# MEGA2560v3ProtoShield.net
KiCad netlist of a schematic drawn in EAGLE
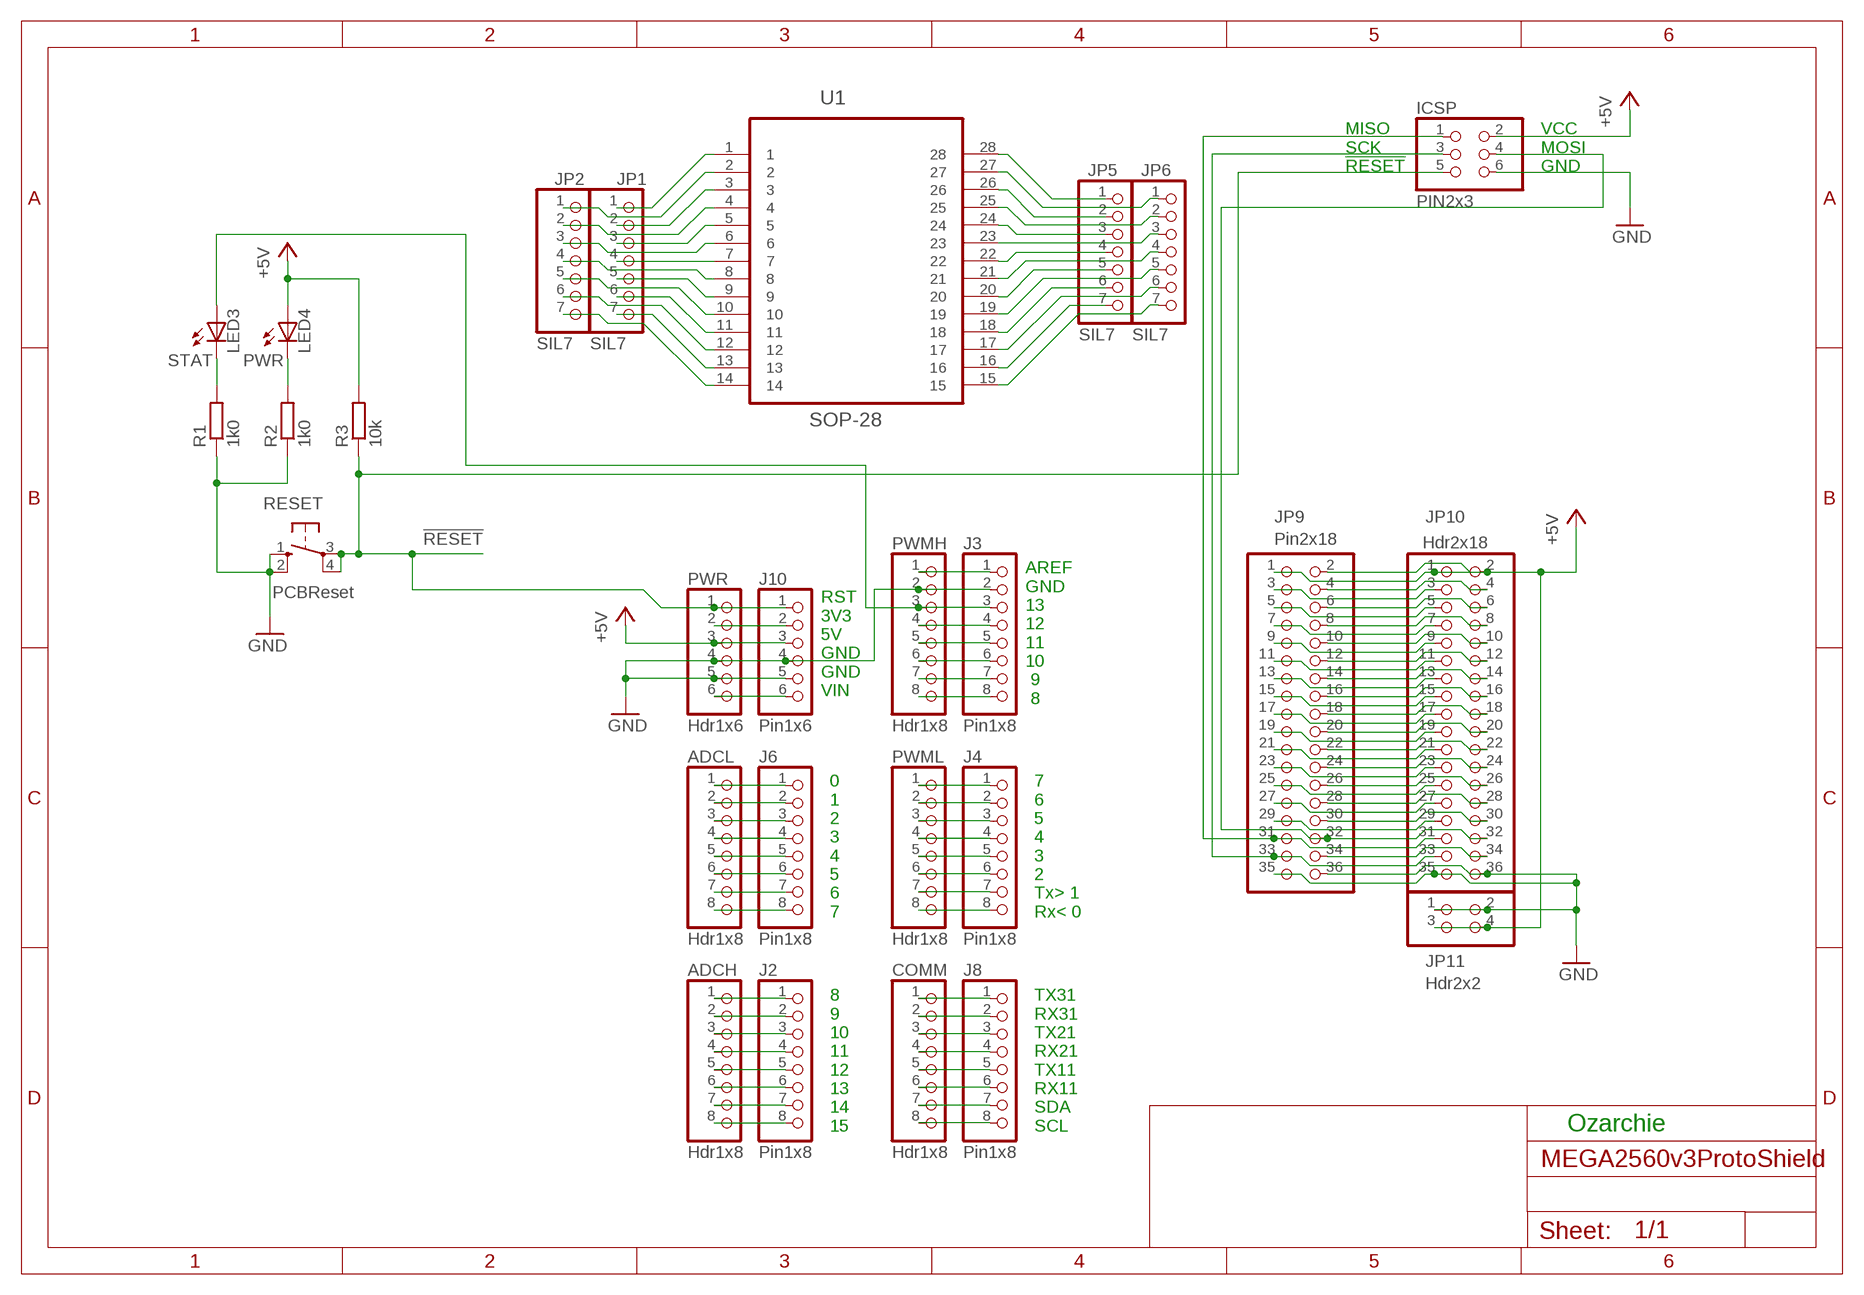
[diagram p0: schematic, sheet 1]

(export (version "E")
  (design (tool "Eeschema 10.0.6"))
  (components
    (comp (ref "ADCH")
      (value "Hdr1x8")
      (footprint "eagle-import:1X08")
      (libsource (lib "eagle-import") (part "PINHD-1X8"))
    )
    (comp (ref "ADCL")
      (value "Hdr1x8")
      (footprint "eagle-import:1X08")
      (libsource (lib "eagle-import") (part "PINHD-1X8"))
    )
    (comp (ref "COMM")
      (value "Hdr1x8")
      (footprint "eagle-import:1X08")
      (libsource (lib "eagle-import") (part "PINHD-1X8"))
    )
    (comp (ref "ICSP")
      (value "PIN2x3")
      (footprint "eagle-import:2X03")
      (libsource (lib "eagle-import") (part "PINHD-2X3"))
    )
    (comp (ref "J2")
      (value "Pin1x8")
      (footprint "eagle-import:1X08")
      (libsource (lib "eagle-import") (part "PINHD-1X8"))
    )
    (comp (ref "J3")
      (value "Pin1x8")
      (footprint "eagle-import:1X08")
      (libsource (lib "eagle-import") (part "PINHD-1X8"))
    )
    (comp (ref "J4")
      (value "Pin1x8")
      (footprint "eagle-import:1X08")
      (libsource (lib "eagle-import") (part "PINHD-1X8"))
    )
    (comp (ref "J6")
      (value "Pin1x8")
      (footprint "eagle-import:1X08")
      (libsource (lib "eagle-import") (part "PINHD-1X8"))
    )
    (comp (ref "J8")
      (value "Pin1x8")
      (footprint "eagle-import:1X08")
      (libsource (lib "eagle-import") (part "PINHD-1X8"))
    )
    (comp (ref "J10")
      (value "Pin1x6")
      (footprint "eagle-import:1X06")
      (libsource (lib "eagle-import") (part "PINHD-1X6"))
    )
    (comp (ref "JP1")
      (value "SIL7")
      (footprint "eagle-import:1X07")
      (libsource (lib "eagle-import") (part "PINHD-1X7"))
    )
    (comp (ref "JP2")
      (value "SIL7")
      (footprint "eagle-import:1X07")
      (libsource (lib "eagle-import") (part "PINHD-1X7"))
    )
    (comp (ref "JP5")
      (value "SIL7")
      (footprint "eagle-import:1X07")
      (libsource (lib "eagle-import") (part "PINHD-1X7"))
    )
    (comp (ref "JP6")
      (value "SIL7")
      (footprint "eagle-import:1X07")
      (libsource (lib "eagle-import") (part "PINHD-1X7"))
    )
    (comp (ref "JP9")
      (value "Pin2x18")
      (footprint "eagle-import:2X18")
      (libsource (lib "eagle-import") (part "PINHD-2X18"))
    )
    (comp (ref "JP10")
      (value "Hdr2x18")
      (footprint "eagle-import:2X18")
      (libsource (lib "eagle-import") (part "PINHD-2X18"))
    )
    (comp (ref "JP11")
      (value "Hdr2x2")
      (footprint "eagle-import:2X02")
      (libsource (lib "eagle-import") (part "PINHD-2X2"))
    )
    (comp (ref "LED3")
      (value "STAT")
      (footprint "eagle-import:CHIPLED_1206")
      (libsource (lib "eagle-import") (part "LEDCHIPLED_1206"))
    )
    (comp (ref "LED4")
      (value "PWR")
      (footprint "eagle-import:CHIPLED_1206")
      (libsource (lib "eagle-import") (part "LEDCHIPLED_1206"))
    )
    (comp (ref "PWMH")
      (value "Hdr1x8")
      (footprint "eagle-import:1X08")
      (libsource (lib "eagle-import") (part "PINHD-1X8"))
    )
    (comp (ref "PWML")
      (value "Hdr1x8")
      (footprint "eagle-import:1X08")
      (libsource (lib "eagle-import") (part "PINHD-1X8"))
    )
    (comp (ref "PWR")
      (value "Hdr1x6")
      (footprint "eagle-import:1X06")
      (libsource (lib "eagle-import") (part "PINHD-1X6"))
    )
    (comp (ref "R1")
      (value "1k0")
      (footprint "eagle-import:R0805")
      (libsource (lib "eagle-import") (part "R-EU_R0805"))
    )
    (comp (ref "R2")
      (value "1k0")
      (footprint "eagle-import:R0805")
      (libsource (lib "eagle-import") (part "R-EU_R0805"))
    )
    (comp (ref "R3")
      (value "10k")
      (footprint "eagle-import:R0805")
      (libsource (lib "eagle-import") (part "R-EU_R0805"))
    )
    (comp (ref "RESET")
      (value "PCBReset")
      (footprint "eagle-import:B3F-10XX")
      (fields (field (name "MPN") "B3F-1000"))
      (libsource (lib "eagle-import") (part "10-XX"))
    )
    (comp (ref "U1")
      (value "SOP-28")
      (footprint "eagle-import:SOP50P1030X264-28N")
      (libsource (lib "eagle-import") (part "SOP-28"))
    )
  )
  (nets
    (net (code "1") (name "+5V") (class "Default")
      (node (ref "ICSP") (pin "2") (pinfunction "2_2") (pintype "passive"))
      (node (ref "J10") (pin "3") (pinfunction "3_3") (pintype "passive"))
      (node (ref "JP10") (pin "1") (pinfunction "1_1") (pintype "passive"))
      (node (ref "JP10") (pin "2") (pinfunction "2_2") (pintype "passive"))
      (node (ref "JP11") (pin "3") (pinfunction "3_3") (pintype "passive"))
      (node (ref "JP11") (pin "4") (pinfunction "4_4") (pintype "passive"))
      (node (ref "JP9") (pin "1") (pinfunction "1_1") (pintype "passive"))
      (node (ref "JP9") (pin "2") (pinfunction "2_2") (pintype "passive"))
      (node (ref "LED4") (pin "A") (pinfunction "A_A") (pintype "passive"))
      (node (ref "PWR") (pin "3") (pinfunction "3_3") (pintype "passive"))
      (node (ref "R3") (pin "2") (pinfunction "2_2") (pintype "passive"))
    )
    (net (code "2") (name "/~{RESET}") (class "Default")
      (node (ref "ICSP") (pin "5") (pinfunction "5_5") (pintype "passive"))
      (node (ref "J10") (pin "1") (pinfunction "1_1") (pintype "passive"))
      (node (ref "PWR") (pin "1") (pinfunction "1_1") (pintype "passive"))
      (node (ref "R3") (pin "1") (pinfunction "1_1") (pintype "passive"))
      (node (ref "RESET") (pin "3") (pinfunction "P_3") (pintype "passive"))
      (node (ref "RESET") (pin "4") (pinfunction "P1_4") (pintype "passive"))
    )
    (net (code "3") (name "GND") (class "Default")
      (node (ref "ICSP") (pin "6") (pinfunction "6_6") (pintype "passive"))
      (node (ref "J10") (pin "4") (pinfunction "4_4") (pintype "passive"))
      (node (ref "J10") (pin "5") (pinfunction "5_5") (pintype "passive"))
      (node (ref "J3") (pin "2") (pinfunction "2_2") (pintype "passive"))
      (node (ref "JP10") (pin "35") (pinfunction "35_35") (pintype "passive"))
      (node (ref "JP10") (pin "36") (pinfunction "36_36") (pintype "passive"))
      (node (ref "JP11") (pin "1") (pinfunction "1_1") (pintype "passive"))
      (node (ref "JP11") (pin "2") (pinfunction "2_2") (pintype "passive"))
      (node (ref "JP9") (pin "35") (pinfunction "35_35") (pintype "passive"))
      (node (ref "JP9") (pin "36") (pinfunction "36_36") (pintype "passive"))
      (node (ref "PWMH") (pin "2") (pinfunction "2_2") (pintype "passive"))
      (node (ref "PWR") (pin "4") (pinfunction "4_4") (pintype "passive"))
      (node (ref "PWR") (pin "5") (pinfunction "5_5") (pintype "passive"))
      (node (ref "R1") (pin "1") (pinfunction "1_1") (pintype "passive"))
      (node (ref "R2") (pin "1") (pinfunction "1_1") (pintype "passive"))
      (node (ref "RESET") (pin "1") (pinfunction "S_1") (pintype "passive"))
      (node (ref "RESET") (pin "2") (pinfunction "S1_2") (pintype "passive"))
    )
    (net (code "4") (name "Net-(ADCH-Pad1)") (class "Default")
      (node (ref "ADCH") (pin "1") (pinfunction "1_1") (pintype "passive"))
      (node (ref "J2") (pin "1") (pinfunction "1_1") (pintype "passive"))
    )
    (net (code "5") (name "Net-(ADCH-Pad2)") (class "Default")
      (node (ref "ADCH") (pin "2") (pinfunction "2_2") (pintype "passive"))
      (node (ref "J2") (pin "2") (pinfunction "2_2") (pintype "passive"))
    )
    (net (code "6") (name "Net-(ADCH-Pad3)") (class "Default")
      (node (ref "ADCH") (pin "3") (pinfunction "3_3") (pintype "passive"))
      (node (ref "J2") (pin "3") (pinfunction "3_3") (pintype "passive"))
    )
    (net (code "7") (name "Net-(ADCH-Pad4)") (class "Default")
      (node (ref "ADCH") (pin "4") (pinfunction "4_4") (pintype "passive"))
      (node (ref "J2") (pin "4") (pinfunction "4_4") (pintype "passive"))
    )
    (net (code "8") (name "Net-(ADCH-Pad5)") (class "Default")
      (node (ref "ADCH") (pin "5") (pinfunction "5_5") (pintype "passive"))
      (node (ref "J2") (pin "5") (pinfunction "5_5") (pintype "passive"))
    )
    (net (code "9") (name "Net-(ADCH-Pad6)") (class "Default")
      (node (ref "ADCH") (pin "6") (pinfunction "6_6") (pintype "passive"))
      (node (ref "J2") (pin "6") (pinfunction "6_6") (pintype "passive"))
    )
    (net (code "10") (name "Net-(ADCH-Pad7)") (class "Default")
      (node (ref "ADCH") (pin "7") (pinfunction "7_7") (pintype "passive"))
      (node (ref "J2") (pin "7") (pinfunction "7_7") (pintype "passive"))
    )
    (net (code "11") (name "Net-(ADCH-Pad8)") (class "Default")
      (node (ref "ADCH") (pin "8") (pinfunction "8_8") (pintype "passive"))
      (node (ref "J2") (pin "8") (pinfunction "8_8") (pintype "passive"))
    )
    (net (code "12") (name "Net-(ADCL-Pad1)") (class "Default")
      (node (ref "ADCL") (pin "1") (pinfunction "1_1") (pintype "passive"))
      (node (ref "J6") (pin "1") (pinfunction "1_1") (pintype "passive"))
    )
    (net (code "13") (name "Net-(ADCL-Pad2)") (class "Default")
      (node (ref "ADCL") (pin "2") (pinfunction "2_2") (pintype "passive"))
      (node (ref "J6") (pin "2") (pinfunction "2_2") (pintype "passive"))
    )
    (net (code "14") (name "Net-(ADCL-Pad3)") (class "Default")
      (node (ref "ADCL") (pin "3") (pinfunction "3_3") (pintype "passive"))
      (node (ref "J6") (pin "3") (pinfunction "3_3") (pintype "passive"))
    )
    (net (code "15") (name "Net-(ADCL-Pad4)") (class "Default")
      (node (ref "ADCL") (pin "4") (pinfunction "4_4") (pintype "passive"))
      (node (ref "J6") (pin "4") (pinfunction "4_4") (pintype "passive"))
    )
    (net (code "16") (name "Net-(ADCL-Pad5)") (class "Default")
      (node (ref "ADCL") (pin "5") (pinfunction "5_5") (pintype "passive"))
      (node (ref "J6") (pin "5") (pinfunction "5_5") (pintype "passive"))
    )
    (net (code "17") (name "Net-(ADCL-Pad6)") (class "Default")
      (node (ref "ADCL") (pin "6") (pinfunction "6_6") (pintype "passive"))
      (node (ref "J6") (pin "6") (pinfunction "6_6") (pintype "passive"))
    )
    (net (code "18") (name "Net-(ADCL-Pad7)") (class "Default")
      (node (ref "ADCL") (pin "7") (pinfunction "7_7") (pintype "passive"))
      (node (ref "J6") (pin "7") (pinfunction "7_7") (pintype "passive"))
    )
    (net (code "19") (name "Net-(ADCL-Pad8)") (class "Default")
      (node (ref "ADCL") (pin "8") (pinfunction "8_8") (pintype "passive"))
      (node (ref "J6") (pin "8") (pinfunction "8_8") (pintype "passive"))
    )
    (net (code "20") (name "Net-(COMM-Pad1)") (class "Default")
      (node (ref "COMM") (pin "1") (pinfunction "1_1") (pintype "passive"))
      (node (ref "J8") (pin "1") (pinfunction "1_1") (pintype "passive"))
    )
    (net (code "21") (name "Net-(COMM-Pad2)") (class "Default")
      (node (ref "COMM") (pin "2") (pinfunction "2_2") (pintype "passive"))
      (node (ref "J8") (pin "2") (pinfunction "2_2") (pintype "passive"))
    )
    (net (code "22") (name "Net-(COMM-Pad3)") (class "Default")
      (node (ref "COMM") (pin "3") (pinfunction "3_3") (pintype "passive"))
      (node (ref "J8") (pin "3") (pinfunction "3_3") (pintype "passive"))
    )
    (net (code "23") (name "Net-(COMM-Pad4)") (class "Default")
      (node (ref "COMM") (pin "4") (pinfunction "4_4") (pintype "passive"))
      (node (ref "J8") (pin "4") (pinfunction "4_4") (pintype "passive"))
    )
    (net (code "24") (name "Net-(COMM-Pad5)") (class "Default")
      (node (ref "COMM") (pin "5") (pinfunction "5_5") (pintype "passive"))
      (node (ref "J8") (pin "5") (pinfunction "5_5") (pintype "passive"))
    )
    (net (code "25") (name "Net-(COMM-Pad6)") (class "Default")
      (node (ref "COMM") (pin "6") (pinfunction "6_6") (pintype "passive"))
      (node (ref "J8") (pin "6") (pinfunction "6_6") (pintype "passive"))
    )
    (net (code "26") (name "Net-(COMM-Pad7)") (class "Default")
      (node (ref "COMM") (pin "7") (pinfunction "7_7") (pintype "passive"))
      (node (ref "J8") (pin "7") (pinfunction "7_7") (pintype "passive"))
    )
    (net (code "27") (name "Net-(COMM-Pad8)") (class "Default")
      (node (ref "COMM") (pin "8") (pinfunction "8_8") (pintype "passive"))
      (node (ref "J8") (pin "8") (pinfunction "8_8") (pintype "passive"))
    )
    (net (code "28") (name "Net-(ICSP-Pad1)") (class "Default")
      (node (ref "ICSP") (pin "1") (pinfunction "1_1") (pintype "passive"))
      (node (ref "JP10") (pin "31") (pinfunction "31_31") (pintype "passive"))
      (node (ref "JP9") (pin "31") (pinfunction "31_31") (pintype "passive"))
    )
    (net (code "29") (name "Net-(ICSP-Pad3)") (class "Default")
      (node (ref "ICSP") (pin "3") (pinfunction "3_3") (pintype "passive"))
      (node (ref "JP10") (pin "33") (pinfunction "33_33") (pintype "passive"))
      (node (ref "JP9") (pin "33") (pinfunction "33_33") (pintype "passive"))
    )
    (net (code "30") (name "Net-(ICSP-Pad4)") (class "Default")
      (node (ref "ICSP") (pin "4") (pinfunction "4_4") (pintype "passive"))
      (node (ref "JP10") (pin "32") (pinfunction "32_32") (pintype "passive"))
      (node (ref "JP9") (pin "32") (pinfunction "32_32") (pintype "passive"))
    )
    (net (code "31") (name "Net-(J3-Pad1)") (class "Default")
      (node (ref "J3") (pin "1") (pinfunction "1_1") (pintype "passive"))
      (node (ref "PWMH") (pin "1") (pinfunction "1_1") (pintype "passive"))
    )
    (net (code "32") (name "Net-(J3-Pad3)") (class "Default")
      (node (ref "J3") (pin "3") (pinfunction "3_3") (pintype "passive"))
      (node (ref "LED3") (pin "A") (pinfunction "A_A") (pintype "passive"))
      (node (ref "PWMH") (pin "3") (pinfunction "3_3") (pintype "passive"))
    )
    (net (code "33") (name "Net-(J3-Pad4)") (class "Default")
      (node (ref "J3") (pin "4") (pinfunction "4_4") (pintype "passive"))
      (node (ref "PWMH") (pin "4") (pinfunction "4_4") (pintype "passive"))
    )
    (net (code "34") (name "Net-(J3-Pad5)") (class "Default")
      (node (ref "J3") (pin "5") (pinfunction "5_5") (pintype "passive"))
      (node (ref "PWMH") (pin "5") (pinfunction "5_5") (pintype "passive"))
    )
    (net (code "35") (name "Net-(J3-Pad6)") (class "Default")
      (node (ref "J3") (pin "6") (pinfunction "6_6") (pintype "passive"))
      (node (ref "PWMH") (pin "6") (pinfunction "6_6") (pintype "passive"))
    )
    (net (code "36") (name "Net-(J3-Pad7)") (class "Default")
      (node (ref "J3") (pin "7") (pinfunction "7_7") (pintype "passive"))
      (node (ref "PWMH") (pin "7") (pinfunction "7_7") (pintype "passive"))
    )
    (net (code "37") (name "Net-(J3-Pad8)") (class "Default")
      (node (ref "J3") (pin "8") (pinfunction "8_8") (pintype "passive"))
      (node (ref "PWMH") (pin "8") (pinfunction "8_8") (pintype "passive"))
    )
    (net (code "38") (name "Net-(J4-Pad1)") (class "Default")
      (node (ref "J4") (pin "1") (pinfunction "1_1") (pintype "passive"))
      (node (ref "PWML") (pin "1") (pinfunction "1_1") (pintype "passive"))
    )
    (net (code "39") (name "Net-(J4-Pad2)") (class "Default")
      (node (ref "J4") (pin "2") (pinfunction "2_2") (pintype "passive"))
      (node (ref "PWML") (pin "2") (pinfunction "2_2") (pintype "passive"))
    )
    (net (code "40") (name "Net-(J4-Pad3)") (class "Default")
      (node (ref "J4") (pin "3") (pinfunction "3_3") (pintype "passive"))
      (node (ref "PWML") (pin "3") (pinfunction "3_3") (pintype "passive"))
    )
    (net (code "41") (name "Net-(J4-Pad4)") (class "Default")
      (node (ref "J4") (pin "4") (pinfunction "4_4") (pintype "passive"))
      (node (ref "PWML") (pin "4") (pinfunction "4_4") (pintype "passive"))
    )
    (net (code "42") (name "Net-(J4-Pad5)") (class "Default")
      (node (ref "J4") (pin "5") (pinfunction "5_5") (pintype "passive"))
      (node (ref "PWML") (pin "5") (pinfunction "5_5") (pintype "passive"))
    )
    (net (code "43") (name "Net-(J4-Pad6)") (class "Default")
      (node (ref "J4") (pin "6") (pinfunction "6_6") (pintype "passive"))
      (node (ref "PWML") (pin "6") (pinfunction "6_6") (pintype "passive"))
    )
    (net (code "44") (name "Net-(J4-Pad7)") (class "Default")
      (node (ref "J4") (pin "7") (pinfunction "7_7") (pintype "passive"))
      (node (ref "PWML") (pin "7") (pinfunction "7_7") (pintype "passive"))
    )
    (net (code "45") (name "Net-(J4-Pad8)") (class "Default")
      (node (ref "J4") (pin "8") (pinfunction "8_8") (pintype "passive"))
      (node (ref "PWML") (pin "8") (pinfunction "8_8") (pintype "passive"))
    )
    (net (code "46") (name "Net-(J10-Pad2)") (class "Default")
      (node (ref "J10") (pin "2") (pinfunction "2_2") (pintype "passive"))
      (node (ref "PWR") (pin "2") (pinfunction "2_2") (pintype "passive"))
    )
    (net (code "47") (name "Net-(J10-Pad6)") (class "Default")
      (node (ref "J10") (pin "6") (pinfunction "6_6") (pintype "passive"))
      (node (ref "PWR") (pin "6") (pinfunction "6_6") (pintype "passive"))
    )
    (net (code "48") (name "Net-(JP1-Pad1)") (class "Default")
      (node (ref "JP1") (pin "1") (pinfunction "1_1") (pintype "passive"))
      (node (ref "U1") (pin "1") (pinfunction "1_1") (pintype "bidirectional"))
    )
    (net (code "49") (name "Net-(JP1-Pad2)") (class "Default")
      (node (ref "JP1") (pin "2") (pinfunction "2_2") (pintype "passive"))
      (node (ref "U1") (pin "3") (pinfunction "3_3") (pintype "bidirectional"))
    )
    (net (code "50") (name "Net-(JP1-Pad3)") (class "Default")
      (node (ref "JP1") (pin "3") (pinfunction "3_3") (pintype "passive"))
      (node (ref "U1") (pin "5") (pinfunction "5_5") (pintype "bidirectional"))
    )
    (net (code "51") (name "Net-(JP1-Pad4)") (class "Default")
      (node (ref "JP1") (pin "4") (pinfunction "4_4") (pintype "passive"))
      (node (ref "U1") (pin "7") (pinfunction "7_7") (pintype "bidirectional"))
    )
    (net (code "52") (name "Net-(JP1-Pad5)") (class "Default")
      (node (ref "JP1") (pin "5") (pinfunction "5_5") (pintype "passive"))
      (node (ref "U1") (pin "9") (pinfunction "9_9") (pintype "bidirectional"))
    )
    (net (code "53") (name "Net-(JP1-Pad6)") (class "Default")
      (node (ref "JP1") (pin "6") (pinfunction "6_6") (pintype "passive"))
      (node (ref "U1") (pin "11") (pinfunction "11_11") (pintype "bidirectional"))
    )
    (net (code "54") (name "Net-(JP1-Pad7)") (class "Default")
      (node (ref "JP1") (pin "7") (pinfunction "7_7") (pintype "passive"))
      (node (ref "U1") (pin "13") (pinfunction "13_13") (pintype "bidirectional"))
    )
    (net (code "55") (name "Net-(JP2-Pad1)") (class "Default")
      (node (ref "JP2") (pin "1") (pinfunction "1_1") (pintype "passive"))
      (node (ref "U1") (pin "2") (pinfunction "2_2") (pintype "bidirectional"))
    )
    (net (code "56") (name "Net-(JP2-Pad2)") (class "Default")
      (node (ref "JP2") (pin "2") (pinfunction "2_2") (pintype "passive"))
      (node (ref "U1") (pin "4") (pinfunction "4_4") (pintype "bidirectional"))
    )
    (net (code "57") (name "Net-(JP2-Pad3)") (class "Default")
      (node (ref "JP2") (pin "3") (pinfunction "3_3") (pintype "passive"))
      (node (ref "U1") (pin "6") (pinfunction "6_6") (pintype "bidirectional"))
    )
    (net (code "58") (name "Net-(JP2-Pad4)") (class "Default")
      (node (ref "JP2") (pin "4") (pinfunction "4_4") (pintype "passive"))
      (node (ref "U1") (pin "8") (pinfunction "8_8") (pintype "bidirectional"))
    )
    (net (code "59") (name "Net-(JP2-Pad5)") (class "Default")
      (node (ref "JP2") (pin "5") (pinfunction "5_5") (pintype "passive"))
      (node (ref "U1") (pin "10") (pinfunction "10_10") (pintype "bidirectional"))
    )
    (net (code "60") (name "Net-(JP2-Pad6)") (class "Default")
      (node (ref "JP2") (pin "6") (pinfunction "6_6") (pintype "passive"))
      (node (ref "U1") (pin "12") (pinfunction "12_12") (pintype "bidirectional"))
    )
    (net (code "61") (name "Net-(JP2-Pad7)") (class "Default")
      (node (ref "JP2") (pin "7") (pinfunction "7_7") (pintype "passive"))
      (node (ref "U1") (pin "14") (pinfunction "14_14") (pintype "bidirectional"))
    )
    (net (code "62") (name "Net-(JP5-Pad1)") (class "Default")
      (node (ref "JP5") (pin "1") (pinfunction "1_1") (pintype "passive"))
      (node (ref "U1") (pin "28") (pinfunction "28_28") (pintype "bidirectional"))
    )
    (net (code "63") (name "Net-(JP5-Pad2)") (class "Default")
      (node (ref "JP5") (pin "2") (pinfunction "2_2") (pintype "passive"))
      (node (ref "U1") (pin "26") (pinfunction "26_26") (pintype "bidirectional"))
    )
    (net (code "64") (name "Net-(JP5-Pad3)") (class "Default")
      (node (ref "JP5") (pin "3") (pinfunction "3_3") (pintype "passive"))
      (node (ref "U1") (pin "24") (pinfunction "24_24") (pintype "bidirectional"))
    )
    (net (code "65") (name "Net-(JP5-Pad4)") (class "Default")
      (node (ref "JP5") (pin "4") (pinfunction "4_4") (pintype "passive"))
      (node (ref "U1") (pin "22") (pinfunction "22_22") (pintype "bidirectional"))
    )
    (net (code "66") (name "Net-(JP5-Pad5)") (class "Default")
      (node (ref "JP5") (pin "5") (pinfunction "5_5") (pintype "passive"))
      (node (ref "U1") (pin "20") (pinfunction "20_20") (pintype "bidirectional"))
    )
    (net (code "67") (name "Net-(JP5-Pad6)") (class "Default")
      (node (ref "JP5") (pin "6") (pinfunction "6_6") (pintype "passive"))
      (node (ref "U1") (pin "18") (pinfunction "18_18") (pintype "bidirectional"))
    )
    (net (code "68") (name "Net-(JP5-Pad7)") (class "Default")
      (node (ref "JP5") (pin "7") (pinfunction "7_7") (pintype "passive"))
      (node (ref "U1") (pin "16") (pinfunction "16_16") (pintype "bidirectional"))
    )
    (net (code "69") (name "Net-(JP6-Pad1)") (class "Default")
      (node (ref "JP6") (pin "1") (pinfunction "1_1") (pintype "passive"))
      (node (ref "U1") (pin "27") (pinfunction "27_27") (pintype "bidirectional"))
    )
    (net (code "70") (name "Net-(JP6-Pad2)") (class "Default")
      (node (ref "JP6") (pin "2") (pinfunction "2_2") (pintype "passive"))
      (node (ref "U1") (pin "25") (pinfunction "25_25") (pintype "bidirectional"))
    )
    (net (code "71") (name "Net-(JP6-Pad3)") (class "Default")
      (node (ref "JP6") (pin "3") (pinfunction "3_3") (pintype "passive"))
      (node (ref "U1") (pin "23") (pinfunction "23_23") (pintype "bidirectional"))
    )
    (net (code "72") (name "Net-(JP6-Pad4)") (class "Default")
      (node (ref "JP6") (pin "4") (pinfunction "4_4") (pintype "passive"))
      (node (ref "U1") (pin "21") (pinfunction "21_21") (pintype "bidirectional"))
    )
    (net (code "73") (name "Net-(JP6-Pad5)") (class "Default")
      (node (ref "JP6") (pin "5") (pinfunction "5_5") (pintype "passive"))
      (node (ref "U1") (pin "19") (pinfunction "19_19") (pintype "bidirectional"))
    )
    (net (code "74") (name "Net-(JP6-Pad6)") (class "Default")
      (node (ref "JP6") (pin "6") (pinfunction "6_6") (pintype "passive"))
      (node (ref "U1") (pin "17") (pinfunction "17_17") (pintype "bidirectional"))
    )
    (net (code "75") (name "Net-(JP6-Pad7)") (class "Default")
      (node (ref "JP6") (pin "7") (pinfunction "7_7") (pintype "passive"))
      (node (ref "U1") (pin "15") (pinfunction "15_15") (pintype "bidirectional"))
    )
    (net (code "76") (name "Net-(JP10-Pad3)") (class "Default")
      (node (ref "JP10") (pin "3") (pinfunction "3_3") (pintype "passive"))
      (node (ref "JP9") (pin "3") (pinfunction "3_3") (pintype "passive"))
    )
    (net (code "77") (name "Net-(JP10-Pad4)") (class "Default")
      (node (ref "JP10") (pin "4") (pinfunction "4_4") (pintype "passive"))
      (node (ref "JP9") (pin "4") (pinfunction "4_4") (pintype "passive"))
    )
    (net (code "78") (name "Net-(JP10-Pad5)") (class "Default")
      (node (ref "JP10") (pin "5") (pinfunction "5_5") (pintype "passive"))
      (node (ref "JP9") (pin "5") (pinfunction "5_5") (pintype "passive"))
    )
    (net (code "79") (name "Net-(JP10-Pad6)") (class "Default")
      (node (ref "JP10") (pin "6") (pinfunction "6_6") (pintype "passive"))
      (node (ref "JP9") (pin "6") (pinfunction "6_6") (pintype "passive"))
    )
    (net (code "80") (name "Net-(JP10-Pad7)") (class "Default")
      (node (ref "JP10") (pin "7") (pinfunction "7_7") (pintype "passive"))
      (node (ref "JP9") (pin "7") (pinfunction "7_7") (pintype "passive"))
    )
    (net (code "81") (name "Net-(JP10-Pad8)") (class "Default")
      (node (ref "JP10") (pin "8") (pinfunction "8_8") (pintype "passive"))
      (node (ref "JP9") (pin "8") (pinfunction "8_8") (pintype "passive"))
    )
    (net (code "82") (name "Net-(JP10-Pad9)") (class "Default")
      (node (ref "JP10") (pin "9") (pinfunction "9_9") (pintype "passive"))
      (node (ref "JP9") (pin "9") (pinfunction "9_9") (pintype "passive"))
    )
    (net (code "83") (name "Net-(JP10-Pad10)") (class "Default")
      (node (ref "JP10") (pin "10") (pinfunction "10_10") (pintype "passive"))
      (node (ref "JP9") (pin "10") (pinfunction "10_10") (pintype "passive"))
    )
    (net (code "84") (name "Net-(JP10-Pad11)") (class "Default")
      (node (ref "JP10") (pin "11") (pinfunction "11_11") (pintype "passive"))
      (node (ref "JP9") (pin "11") (pinfunction "11_11") (pintype "passive"))
    )
    (net (code "85") (name "Net-(JP10-Pad12)") (class "Default")
      (node (ref "JP10") (pin "12") (pinfunction "12_12") (pintype "passive"))
      (node (ref "JP9") (pin "12") (pinfunction "12_12") (pintype "passive"))
    )
    (net (code "86") (name "Net-(JP10-Pad13)") (class "Default")
      (node (ref "JP10") (pin "13") (pinfunction "13_13") (pintype "passive"))
      (node (ref "JP9") (pin "13") (pinfunction "13_13") (pintype "passive"))
    )
    (net (code "87") (name "Net-(JP10-Pad14)") (class "Default")
      (node (ref "JP10") (pin "14") (pinfunction "14_14") (pintype "passive"))
      (node (ref "JP9") (pin "14") (pinfunction "14_14") (pintype "passive"))
    )
    (net (code "88") (name "Net-(JP10-Pad15)") (class "Default")
      (node (ref "JP10") (pin "15") (pinfunction "15_15") (pintype "passive"))
      (node (ref "JP9") (pin "15") (pinfunction "15_15") (pintype "passive"))
    )
    (net (code "89") (name "Net-(JP10-Pad16)") (class "Default")
      (node (ref "JP10") (pin "16") (pinfunction "16_16") (pintype "passive"))
      (node (ref "JP9") (pin "16") (pinfunction "16_16") (pintype "passive"))
    )
    (net (code "90") (name "Net-(JP10-Pad17)") (class "Default")
      (node (ref "JP10") (pin "17") (pinfunction "17_17") (pintype "passive"))
      (node (ref "JP9") (pin "17") (pinfunction "17_17") (pintype "passive"))
    )
    (net (code "91") (name "Net-(JP10-Pad18)") (class "Default")
      (node (ref "JP10") (pin "18") (pinfunction "18_18") (pintype "passive"))
      (node (ref "JP9") (pin "18") (pinfunction "18_18") (pintype "passive"))
    )
    (net (code "92") (name "Net-(JP10-Pad19)") (class "Default")
      (node (ref "JP10") (pin "19") (pinfunction "19_19") (pintype "passive"))
      (node (ref "JP9") (pin "19") (pinfunction "19_19") (pintype "passive"))
    )
    (net (code "93") (name "Net-(JP10-Pad20)") (class "Default")
      (node (ref "JP10") (pin "20") (pinfunction "20_20") (pintype "passive"))
      (node (ref "JP9") (pin "20") (pinfunction "20_20") (pintype "passive"))
    )
    (net (code "94") (name "Net-(JP10-Pad21)") (class "Default")
      (node (ref "JP10") (pin "21") (pinfunction "21_21") (pintype "passive"))
      (node (ref "JP9") (pin "21") (pinfunction "21_21") (pintype "passive"))
    )
    (net (code "95") (name "Net-(JP10-Pad22)") (class "Default")
      (node (ref "JP10") (pin "22") (pinfunction "22_22") (pintype "passive"))
      (node (ref "JP9") (pin "22") (pinfunction "22_22") (pintype "passive"))
    )
    (net (code "96") (name "Net-(JP10-Pad23)") (class "Default")
      (node (ref "JP10") (pin "23") (pinfunction "23_23") (pintype "passive"))
      (node (ref "JP9") (pin "23") (pinfunction "23_23") (pintype "passive"))
    )
    (net (code "97") (name "Net-(JP10-Pad24)") (class "Default")
      (node (ref "JP10") (pin "24") (pinfunction "24_24") (pintype "passive"))
      (node (ref "JP9") (pin "24") (pinfunction "24_24") (pintype "passive"))
    )
    (net (code "98") (name "Net-(JP10-Pad25)") (class "Default")
      (node (ref "JP10") (pin "25") (pinfunction "25_25") (pintype "passive"))
      (node (ref "JP9") (pin "25") (pinfunction "25_25") (pintype "passive"))
    )
    (net (code "99") (name "Net-(JP10-Pad26)") (class "Default")
      (node (ref "JP10") (pin "26") (pinfunction "26_26") (pintype "passive"))
      (node (ref "JP9") (pin "26") (pinfunction "26_26") (pintype "passive"))
    )
    (net (code "100") (name "Net-(JP10-Pad27)") (class "Default")
      (node (ref "JP10") (pin "27") (pinfunction "27_27") (pintype "passive"))
      (node (ref "JP9") (pin "27") (pinfunction "27_27") (pintype "passive"))
    )
    (net (code "101") (name "Net-(JP10-Pad28)") (class "Default")
      (node (ref "JP10") (pin "28") (pinfunction "28_28") (pintype "passive"))
      (node (ref "JP9") (pin "28") (pinfunction "28_28") (pintype "passive"))
    )
    (net (code "102") (name "Net-(JP10-Pad29)") (class "Default")
      (node (ref "JP10") (pin "29") (pinfunction "29_29") (pintype "passive"))
      (node (ref "JP9") (pin "29") (pinfunction "29_29") (pintype "passive"))
    )
    (net (code "103") (name "Net-(JP10-Pad30)") (class "Default")
      (node (ref "JP10") (pin "30") (pinfunction "30_30") (pintype "passive"))
      (node (ref "JP9") (pin "30") (pinfunction "30_30") (pintype "passive"))
    )
    (net (code "104") (name "Net-(JP10-Pad34)") (class "Default")
      (node (ref "JP10") (pin "34") (pinfunction "34_34") (pintype "passive"))
      (node (ref "JP9") (pin "34") (pinfunction "34_34") (pintype "passive"))
    )
    (net (code "105") (name "Net-(LED3-PadC)") (class "Default")
      (node (ref "LED3") (pin "C") (pinfunction "C_C") (pintype "passive"))
      (node (ref "R1") (pin "2") (pinfunction "2_2") (pintype "passive"))
    )
    (net (code "106") (name "Net-(LED4-PadC)") (class "Default")
      (node (ref "LED4") (pin "C") (pinfunction "C_C") (pintype "passive"))
      (node (ref "R2") (pin "2") (pinfunction "2_2") (pintype "passive"))
    )
  )
)
